# voltageRegulator.net
KiCad netlist of a schematic drawn in Altium Designer
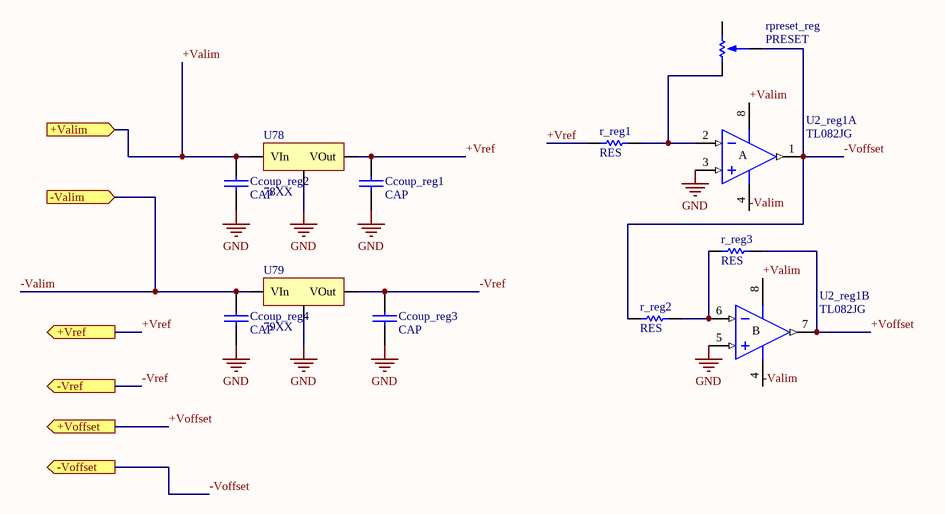
[diagram p0: voltageRegulator.SchDoc]

(export (version "E")
  (design (tool "Eeschema 10.0.6"))
  (components
    (comp (ref "Ccoup_reg1") (value "CAP") (footprint "CAP200") (libsource (lib "LIBEBAL") (part "CAP")))
    (comp (ref "Ccoup_reg2") (value "CAP") (footprint "CAP200") (libsource (lib "LIBEBAL") (part "CAP")))
    (comp (ref "Ccoup_reg3") (value "CAP") (footprint "CAP200") (libsource (lib "LIBEBAL") (part "CAP")))
    (comp (ref "Ccoup_reg4") (value "CAP") (footprint "CAP200") (libsource (lib "LIBEBAL") (part "CAP")))
    (comp (ref "rpreset_reg")
      (value "PRESET")
      (footprint "PRESET V")
      (libsource (lib "LIBEBAL") (part "PRESET"))
    )
    (comp (ref "r_reg1") (value "RES") (footprint "RES300") (libsource (lib "LIBEBAL") (part "RES")))
    (comp (ref "r_reg2") (value "RES") (footprint "RES300") (libsource (lib "LIBEBAL") (part "RES")))
    (comp (ref "r_reg3") (value "RES") (footprint "RES300") (libsource (lib "LIBEBAL") (part "RES")))
    (comp (ref "U2_reg1")
      (value "TL082JG")
      (footprint "JG008")
      (description "JFET-Input Operational Amplifier")
      (fields (field (name "PUBLISHER") "Altium Limited"))
      (libsource (lib "TI Operational Amplifier") (part "TL082JG"))
    )
    (comp (ref "U78")
      (value "78XX")
      (footprint "TO-220 H - DISIPADOR")
      (description "REGULDOR POSITIVO")
      (libsource (lib "LIBEBAL") (part "78XX"))
    )
    (comp (ref "U79")
      (value "79XX")
      (footprint "TO-220 H - DISIPADOR")
      (description "REGULADOR NEGATIVO")
      (libsource (lib "LIBEBAL") (part "79XX"))
    )
  )
  (nets
    (net (code "1") (name "/+Valim") (class "Default")
      (node (ref "Ccoup_reg2") (pin "1") (pinfunction "1_1") (pintype "passive"))
      (node (ref "U2_reg1") (pin "8") (pinfunction "V+_8") (pintype "power_in"))
      (node (ref "U78") (pin "1") (pinfunction "VIn_1") (pintype "passive"))
    )
    (net (code "2") (name "/+Voffset") (class "Default")
      (node (ref "U2_reg1") (pin "7") (pinfunction "OUT_7") (pintype "output"))
      (node (ref "r_reg3") (pin "2") (pinfunction "2_2") (pintype "passive"))
    )
    (net (code "3") (name "/+Vref") (class "Default")
      (node (ref "Ccoup_reg1") (pin "1") (pinfunction "1_1") (pintype "passive"))
      (node (ref "U78") (pin "3") (pinfunction "VOut_3") (pintype "passive"))
      (node (ref "r_reg1") (pin "1") (pinfunction "1_1") (pintype "passive"))
    )
    (net (code "4") (name "/-Valim") (class "Default")
      (node (ref "Ccoup_reg4") (pin "1") (pinfunction "1_1") (pintype "passive"))
      (node (ref "U2_reg1") (pin "4") (pinfunction "V-_4") (pintype "power_in"))
      (node (ref "U79") (pin "2") (pinfunction "VIn_2") (pintype "passive"))
    )
    (net (code "5") (name "/-Voffset") (class "Default")
      (node (ref "U2_reg1") (pin "1") (pinfunction "OUT_1") (pintype "output"))
      (node (ref "r_reg2") (pin "1") (pinfunction "1_1") (pintype "passive"))
      (node (ref "rpreset_reg") (pin "2") (pinfunction "2_2") (pintype "passive"))
    )
    (net (code "6") (name "/-Vref") (class "Default")
      (node (ref "Ccoup_reg3") (pin "1") (pinfunction "1_1") (pintype "passive"))
      (node (ref "U79") (pin "3") (pinfunction "VOut_3") (pintype "passive"))
    )
    (net (code "7") (name "GND") (class "Default")
      (node (ref "Ccoup_reg1") (pin "2") (pinfunction "2_2") (pintype "passive"))
      (node (ref "Ccoup_reg2") (pin "2") (pinfunction "2_2") (pintype "passive"))
      (node (ref "Ccoup_reg3") (pin "2") (pinfunction "2_2") (pintype "passive"))
      (node (ref "Ccoup_reg4") (pin "2") (pinfunction "2_2") (pintype "passive"))
      (node (ref "U2_reg1") (pin "3") (pinfunction "IN+_3") (pintype "input"))
      (node (ref "U2_reg1") (pin "5") (pinfunction "IN+_5") (pintype "input"))
      (node (ref "U78") (pin "2") (pinfunction "GND_2") (pintype "passive"))
      (node (ref "U79") (pin "1") (pinfunction "GND_1") (pintype "passive"))
    )
    (net (code "8") (name "Net-(U2_reg1A-IN-)") (class "Default")
      (node (ref "U2_reg1") (pin "2") (pinfunction "IN-_2") (pintype "input"))
      (node (ref "r_reg1") (pin "2") (pinfunction "2_2") (pintype "passive"))
      (node (ref "rpreset_reg") (pin "3") (pinfunction "3_3") (pintype "passive"))
    )
    (net (code "9") (name "Net-(U2_reg1B-IN-)") (class "Default")
      (node (ref "U2_reg1") (pin "6") (pinfunction "IN-_6") (pintype "input"))
      (node (ref "r_reg2") (pin "2") (pinfunction "2_2") (pintype "passive"))
      (node (ref "r_reg3") (pin "1") (pinfunction "1_1") (pintype "passive"))
    )
    (net (code "10") (name "unconnected-(rpreset_reg-Pad1)") (class "Default")
      (node (ref "rpreset_reg") (pin "1") (pinfunction "1_1") (pintype "passive"))
    )
  )
)
